# 03-FT601.net
KiCad netlist of a schematic drawn in Altium Designer
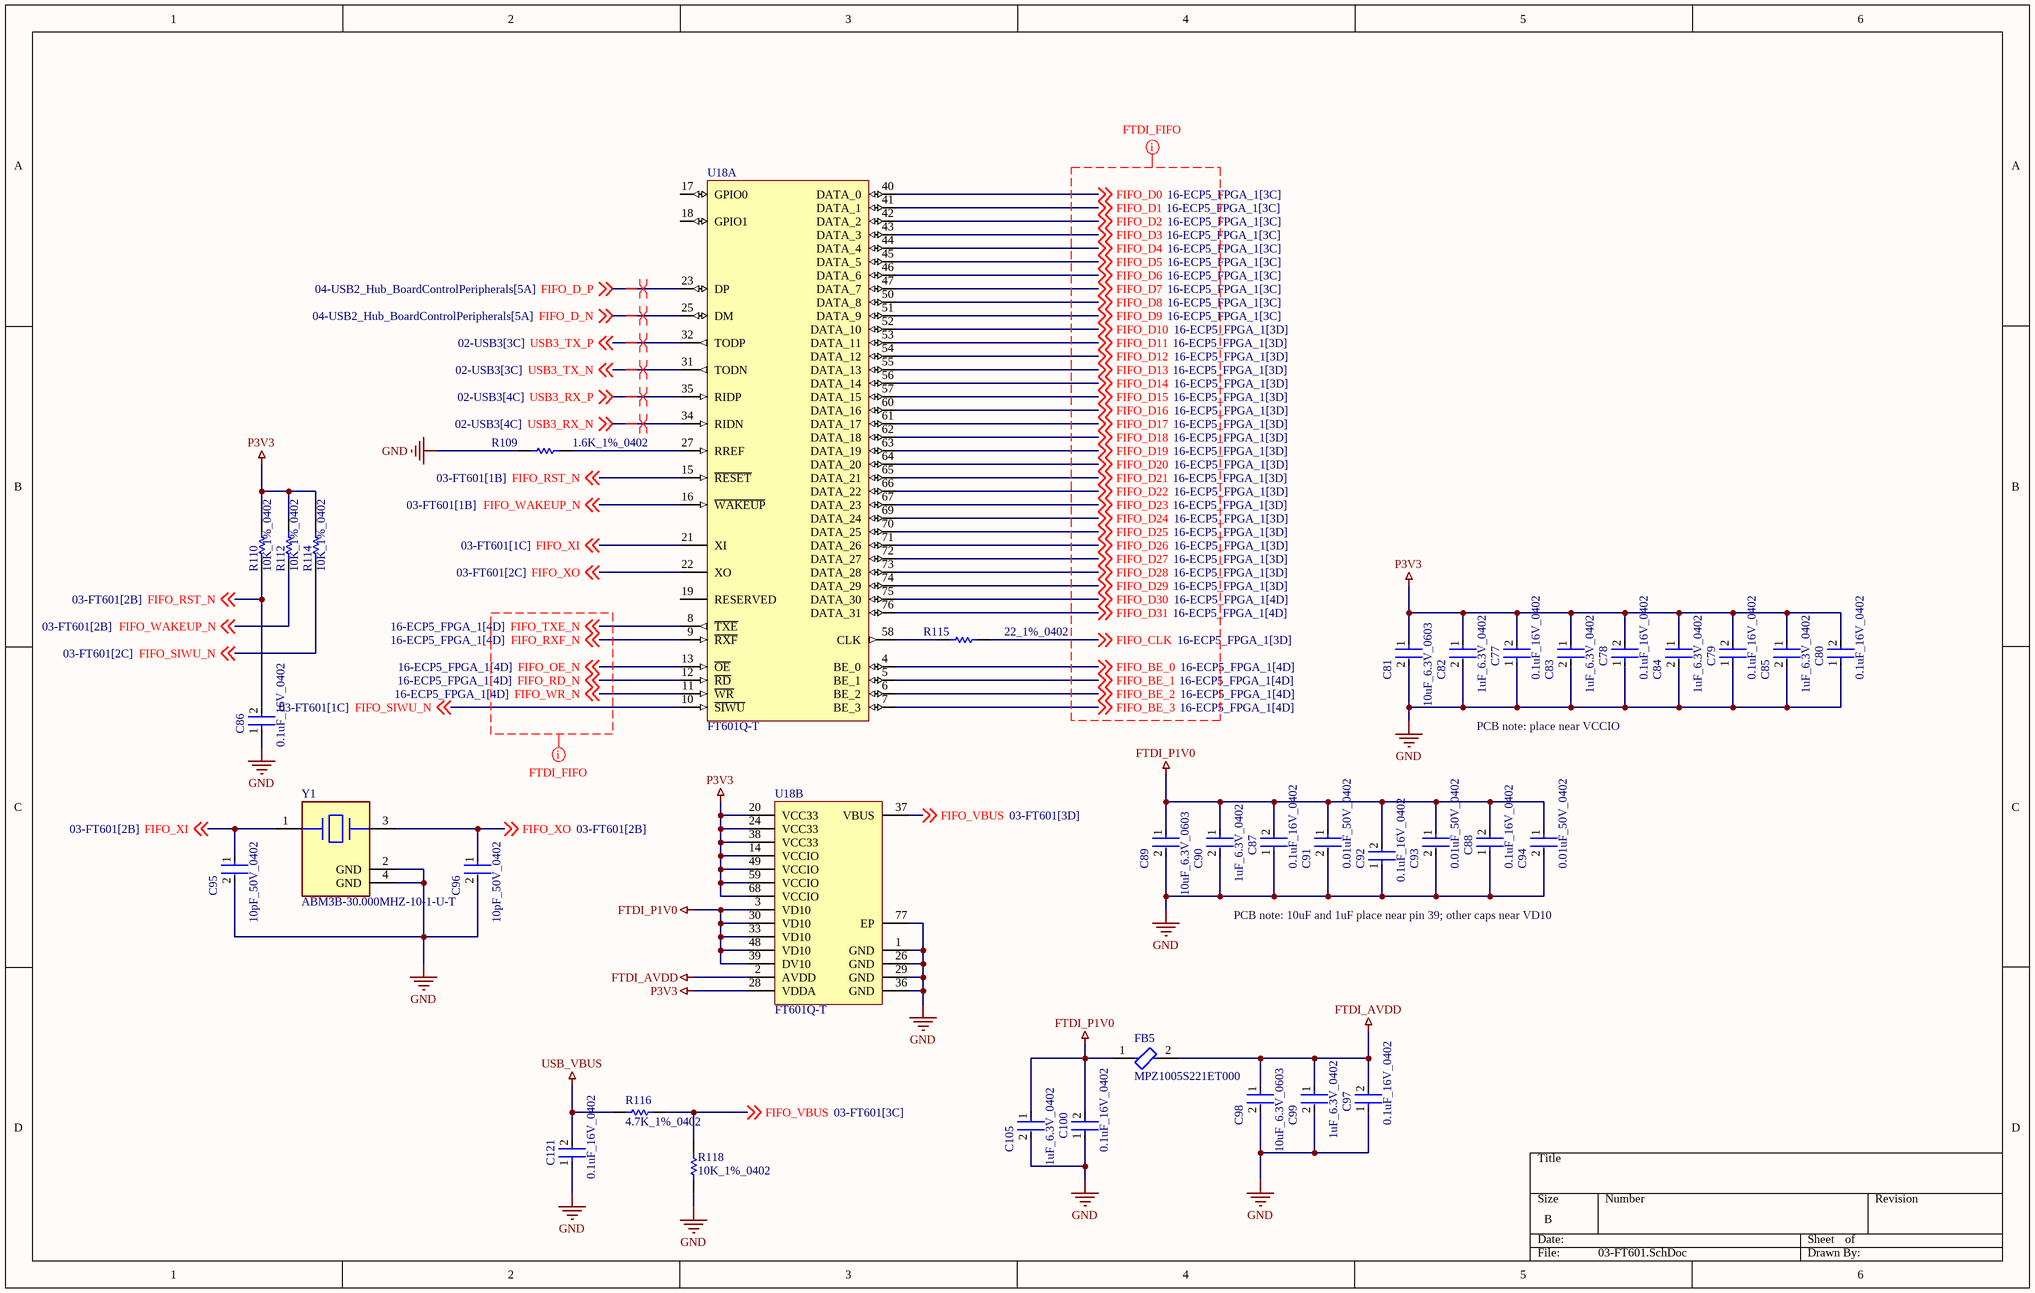
[diagram p0: 03-FT601.SchDoc]

(export (version "E")
  (design (tool "Eeschema 10.0.6"))
  (components
    (comp (ref "C77")
      (value "0.1uF_16V_0402")
      (footprint "FP-C0402-BB-MFG")
      (description "CAP CER 0.1UF 16V 5% X7R 0402")
      (fields
        (field (name "MANUFACTURER") "Kemet")
        (field (name "MANUFACTURER PART NUMBER") "C0402C104J4RACTU")
      )
      (libsource (lib "Altium Content Vault") (part "b4654b650e69147ec39a6b967a45e02"))
    )
    (comp (ref "C78")
      (value "0.1uF_16V_0402")
      (footprint "FP-C0402-BB-MFG")
      (description "CAP CER 0.1UF 16V 5% X7R 0402")
      (fields
        (field (name "MANUFACTURER") "Kemet")
        (field (name "MANUFACTURER PART NUMBER") "C0402C104J4RACTU")
      )
      (libsource (lib "Altium Content Vault") (part "b4654b650e69147ec39a6b967a45e02"))
    )
    (comp (ref "C79")
      (value "0.1uF_16V_0402")
      (footprint "FP-C0402-BB-MFG")
      (description "CAP CER 0.1UF 16V 5% X7R 0402")
      (fields
        (field (name "MANUFACTURER") "Kemet")
        (field (name "MANUFACTURER PART NUMBER") "C0402C104J4RACTU")
      )
      (libsource (lib "Altium Content Vault") (part "b4654b650e69147ec39a6b967a45e02"))
    )
    (comp (ref "C80")
      (value "0.1uF_16V_0402")
      (footprint "FP-C0402-BB-MFG")
      (description "CAP CER 0.1UF 16V 5% X7R 0402")
      (fields
        (field (name "MANUFACTURER") "Kemet")
        (field (name "MANUFACTURER PART NUMBER") "C0402C104J4RACTU")
      )
      (libsource (lib "Altium Content Vault") (part "b4654b650e69147ec39a6b967a45e02"))
    )
    (comp (ref "C81")
      (value "10uF_6.3V_0603")
      (footprint "FP-GRM188-0_1-e0_2_0_55-IPC_A")
      (description "Chip Multilayer Ceramic Capacitors for General Purpose, 0603, 10uF, X5R, 15%, 20%, 6.3V")
      (fields (field (name "VOLTAGE") "6.3V") (field (name "TOLERANCE") "20%"))
      (libsource (lib "Altium Content Vault") (part "02cd4be3c70576c341d710602a673aa"))
    )
    (comp (ref "C82")
      (value "1uF_6.3V_0402")
      (footprint "FP-CC0402-MFG")
      (description "CAP CER 1UF 6.3V X5R 0402")
      (fields
        (field (name "MANUFACTURER") "YAGEO")
        (field (name "OCTOPART") "https://octopart.com/cc0402krx5r5bb105-yageo-42244618")
      )
      (libsource (lib "Altium Content Vault") (part "11868f565c42a9108669ba33697ecf6"))
    )
    (comp (ref "C83")
      (value "1uF_6.3V_0402")
      (footprint "FP-CC0402-MFG")
      (description "CAP CER 1UF 6.3V X5R 0402")
      (fields
        (field (name "MANUFACTURER") "YAGEO")
        (field (name "OCTOPART") "https://octopart.com/cc0402krx5r5bb105-yageo-42244618")
      )
      (libsource (lib "Altium Content Vault") (part "11868f565c42a9108669ba33697ecf6"))
    )
    (comp (ref "C84")
      (value "1uF_6.3V_0402")
      (footprint "FP-CC0402-MFG")
      (description "CAP CER 1UF 6.3V X5R 0402")
      (fields
        (field (name "MANUFACTURER") "YAGEO")
        (field (name "OCTOPART") "https://octopart.com/cc0402krx5r5bb105-yageo-42244618")
      )
      (libsource (lib "Altium Content Vault") (part "11868f565c42a9108669ba33697ecf6"))
    )
    (comp (ref "C85")
      (value "1uF_6.3V_0402")
      (footprint "FP-CC0402-MFG")
      (description "CAP CER 1UF 6.3V X5R 0402")
      (fields
        (field (name "MANUFACTURER") "YAGEO")
        (field (name "OCTOPART") "https://octopart.com/cc0402krx5r5bb105-yageo-42244618")
      )
      (libsource (lib "Altium Content Vault") (part "11868f565c42a9108669ba33697ecf6"))
    )
    (comp (ref "C86")
      (value "0.1uF_16V_0402")
      (footprint "FP-C0402-BB-MFG")
      (description "CAP CER 0.1UF 16V 5% X7R 0402")
      (fields
        (field (name "MANUFACTURER") "Kemet")
        (field (name "MANUFACTURER PART NUMBER") "C0402C104J4RACTU")
      )
      (libsource (lib "Altium Content Vault") (part "b4654b650e69147ec39a6b967a45e02"))
    )
    (comp (ref "C87")
      (value "0.1uF_16V_0402")
      (footprint "FP-C0402-BB-MFG")
      (description "CAP CER 0.1UF 16V 5% X7R 0402")
      (fields
        (field (name "MANUFACTURER") "Kemet")
        (field (name "MANUFACTURER PART NUMBER") "C0402C104J4RACTU")
      )
      (libsource (lib "Altium Content Vault") (part "b4654b650e69147ec39a6b967a45e02"))
    )
    (comp (ref "C88")
      (value "0.1uF_16V_0402")
      (footprint "FP-C0402-BB-MFG")
      (description "CAP CER 0.1UF 16V 5% X7R 0402")
      (fields
        (field (name "MANUFACTURER") "Kemet")
        (field (name "MANUFACTURER PART NUMBER") "C0402C104J4RACTU")
      )
      (libsource (lib "Altium Content Vault") (part "b4654b650e69147ec39a6b967a45e02"))
    )
    (comp (ref "C89")
      (value "10uF_6.3V_0603")
      (footprint "FP-GRM188-0_1-e0_2_0_55-IPC_A")
      (description "Chip Multilayer Ceramic Capacitors for General Purpose, 0603, 10uF, X5R, 15%, 20%, 6.3V")
      (fields (field (name "VOLTAGE") "6.3V") (field (name "TOLERANCE") "20%"))
      (libsource (lib "Altium Content Vault") (part "02cd4be3c70576c341d710602a673aa"))
    )
    (comp (ref "C90")
      (value "1uF_6.3V_0402")
      (footprint "FP-CC0402-MFG")
      (description "CAP CER 1UF 6.3V X5R 0402")
      (fields
        (field (name "MANUFACTURER") "YAGEO")
        (field (name "OCTOPART") "https://octopart.com/cc0402krx5r5bb105-yageo-42244618")
      )
      (libsource (lib "Altium Content Vault") (part "11868f565c42a9108669ba33697ecf6"))
    )
    (comp (ref "C91")
      (value "0.01uF_50V_0402")
      (footprint "FP-C0402-BB-MFG")
      (description "CAP CER 10000PF 50V X7R 0402")
      (fields (field (name "TOLERANCE") "0.1") (field (name "MANUFACTURER") "Kemet"))
      (libsource (lib "Altium Content Vault") (part "b4654b650e69147ec39a6b967a45e02"))
    )
    (comp (ref "C92")
      (value "0.1uF_16V_0402")
      (footprint "FP-C0402-BB-MFG")
      (description "CAP CER 0.1UF 16V 5% X7R 0402")
      (fields
        (field (name "MANUFACTURER") "Kemet")
        (field (name "MANUFACTURER PART NUMBER") "C0402C104J4RACTU")
      )
      (libsource (lib "Altium Content Vault") (part "b4654b650e69147ec39a6b967a45e02"))
    )
    (comp (ref "C93")
      (value "0.01uF_50V_0402")
      (footprint "FP-C0402-BB-MFG")
      (description "CAP CER 10000PF 50V X7R 0402")
      (fields (field (name "TOLERANCE") "0.1") (field (name "MANUFACTURER") "Kemet"))
      (libsource (lib "Altium Content Vault") (part "b4654b650e69147ec39a6b967a45e02"))
    )
    (comp (ref "C94")
      (value "0.01uF_50V_0402")
      (footprint "FP-C0402-BB-MFG")
      (description "CAP CER 10000PF 50V X7R 0402")
      (fields (field (name "TOLERANCE") "0.1") (field (name "MANUFACTURER") "Kemet"))
      (libsource (lib "Altium Content Vault") (part "b4654b650e69147ec39a6b967a45e02"))
    )
    (comp (ref "C95")
      (value "10pF_50V_0402")
      (footprint "FP-C0402-BB-MFG")
      (fields
        (field (name "MANUFACTURER PART NUMBER") "C0402C100J5GACTU")
        (field (name "MANUFACTURER") "Kemet")
        (field (name "OCTOPART") "https://octopart.com/c0402c100j5gactu-kemet-108448")
      )
      (libsource (lib "Altium Content Vault") (part "b4654b650e69147ec39a6b967a45e02"))
    )
    (comp (ref "C96")
      (value "10pF_50V_0402")
      (footprint "FP-C0402-BB-MFG")
      (fields
        (field (name "MANUFACTURER PART NUMBER") "C0402C100J5GACTU")
        (field (name "MANUFACTURER") "Kemet")
        (field (name "OCTOPART") "https://octopart.com/c0402c100j5gactu-kemet-108448")
      )
      (libsource (lib "Altium Content Vault") (part "b4654b650e69147ec39a6b967a45e02"))
    )
    (comp (ref "C97")
      (value "0.1uF_16V_0402")
      (footprint "FP-C0402-BB-MFG")
      (description "CAP CER 0.1UF 16V 5% X7R 0402")
      (fields
        (field (name "MANUFACTURER") "Kemet")
        (field (name "MANUFACTURER PART NUMBER") "C0402C104J4RACTU")
      )
      (libsource (lib "Altium Content Vault") (part "b4654b650e69147ec39a6b967a45e02"))
    )
    (comp (ref "C98")
      (value "10uF_6.3V_0603")
      (footprint "FP-GRM188-0_1-e0_2_0_55-IPC_A")
      (description "Chip Multilayer Ceramic Capacitors for General Purpose, 0603, 10uF, X5R, 15%, 20%, 6.3V")
      (fields (field (name "VOLTAGE") "6.3V") (field (name "TOLERANCE") "20%"))
      (libsource (lib "Altium Content Vault") (part "02cd4be3c70576c341d710602a673aa"))
    )
    (comp (ref "C99")
      (value "1uF_6.3V_0402")
      (footprint "FP-CC0402-MFG")
      (description "CAP CER 1UF 6.3V X5R 0402")
      (fields
        (field (name "MANUFACTURER") "YAGEO")
        (field (name "OCTOPART") "https://octopart.com/cc0402krx5r5bb105-yageo-42244618")
      )
      (libsource (lib "Altium Content Vault") (part "11868f565c42a9108669ba33697ecf6"))
    )
    (comp (ref "C100")
      (value "0.1uF_16V_0402")
      (footprint "FP-C0402-BB-MFG")
      (description "CAP CER 0.1UF 16V 5% X7R 0402")
      (fields
        (field (name "MANUFACTURER") "Kemet")
        (field (name "MANUFACTURER PART NUMBER") "C0402C104J4RACTU")
      )
      (libsource (lib "Altium Content Vault") (part "b4654b650e69147ec39a6b967a45e02"))
    )
    (comp (ref "C105")
      (value "1uF_6.3V_0402")
      (footprint "FP-CC0402-MFG")
      (description "CAP CER 1UF 6.3V X5R 0402")
      (fields
        (field (name "MANUFACTURER") "YAGEO")
        (field (name "OCTOPART") "https://octopart.com/cc0402krx5r5bb105-yageo-42244618")
      )
      (libsource (lib "Altium Content Vault") (part "11868f565c42a9108669ba33697ecf6"))
    )
    (comp (ref "C121")
      (value "0.1uF_16V_0402")
      (footprint "FP-C0402-BB-MFG")
      (description "CAP CER 0.1UF 16V 5% X7R 0402")
      (fields
        (field (name "MANUFACTURER") "Kemet")
        (field (name "MANUFACTURER PART NUMBER") "C0402C104J4RACTU")
      )
      (libsource (lib "Altium Content Vault") (part "b4654b650e69147ec39a6b967a45e02"))
    )
    (comp (ref "FB5")
      (value "MPZ1005S221ET000")
      (footprint "FP-MPZ1005-IPC_A")
      (description "Power line Ferrite Bead 220Ω @ 100MHz 0.9A DCR 0.22Ω SMD 0402")
      (fields (field (name "TOLERANCE") "25%"))
      (libsource (lib "Altium Content Vault") (part "5f30dd21d616792df468990f7003faa"))
    )
    (comp (ref "R109")
      (value "1.6K_1%_0402")
      (footprint "RESC1005X40X25LL05T05")
      (fields (field (name "MANUFACTURER") "Panasonic") (field (name "PART NUMBER") "ERJ-2RKF1601X"))
      (libsource (lib "Altium Content Vault") (part "RES"))
    )
    (comp (ref "R110")
      (value "10K_1%_0402")
      (footprint "RESC1005X40X25NL10T10")
      (fields (field (name "MANUFACTURER") "Bourns") (field (name "PART NUMBER") "CR0402-FX-1002GLF"))
      (libsource (lib "Altium Content Vault") (part "RES"))
    )
    (comp (ref "R112")
      (value "10K_1%_0402")
      (footprint "RESC1005X40X25NL10T10")
      (fields (field (name "MANUFACTURER") "Bourns") (field (name "PART NUMBER") "CR0402-FX-1002GLF"))
      (libsource (lib "Altium Content Vault") (part "RES"))
    )
    (comp (ref "R114")
      (value "10K_1%_0402")
      (footprint "RESC1005X40X25NL10T10")
      (fields (field (name "MANUFACTURER") "Bourns") (field (name "PART NUMBER") "CR0402-FX-1002GLF"))
      (libsource (lib "Altium Content Vault") (part "RES"))
    )
    (comp (ref "R115")
      (value "22_1%_0402")
      (footprint "RESC1005X40X25ML05T05")
      (description "Chip Resistor, 22 Ohm, +/- 1%, 0.1 W, -55 to 155 degC, 0402 (1005 Metric), RoHS, Tape and Reel")
      (fields (field (name "PARTNUMBER") "ERJ-2RKF22R0X") (field (name "TOLERANCE") "1%"))
      (libsource (lib "Altium Content Vault") (part "RES-2"))
    )
    (comp (ref "R116")
      (value "4.7K_1%_0402")
      (footprint "RESC1005X40X25NL05T10")
      (fields (field (name "MANUFACTURER") "Yageo / Phycomp") (field (name "PART NUMBER") "RC0402FR-074K7L"))
      (libsource (lib "Altium Content Vault") (part "RES"))
    )
    (comp (ref "R118")
      (value "10K_1%_0402")
      (footprint "RESC1005X40X25NL10T10")
      (fields (field (name "MANUFACTURER") "Bourns") (field (name "PART NUMBER") "CR0402-FX-1002GLF"))
      (libsource (lib "Altium Content Vault") (part "RES"))
    )
    (comp (ref "U18")
      (value "FT601Q-T")
      (footprint "FTDI-QFN-76_M")
      (description "32 Bit USB 3.0 to FIFO Bridge, 5 Gbps, 3 to 3.6 V, -40 to 85 degC, 76-Pin QFN, Pb-Free, Tray")
      (libsource (lib "Altium Content Vault") (part "FTDI-FT601Q-QFN-76"))
    )
    (comp (ref "Y1")
      (value "ABM3B-30.000MHZ-10-1-U-T")
      (footprint "FP-ABM3B-MFG")
      (description "Crystal 30MHz ±10ppm 10pF SMD-4 5mm x 3.2mm")
      (fields (field (name "TOLERANCE") "10ppm"))
      (libsource (lib "Altium Content Vault") (part "48e526d86b7f2615d98721063c72f49"))
    )
  )
  (nets
    (net (code "1") (name "FIFO_BE_0") (class "Default")
      (node (ref "U18") (pin "4") (pinfunction "BE_0_4") (pintype "bidirectional"))
    )
    (net (code "2") (name "FIFO_BE_1") (class "Default")
      (node (ref "U18") (pin "5") (pinfunction "BE_1_5") (pintype "bidirectional"))
    )
    (net (code "3") (name "FIFO_BE_2") (class "Default")
      (node (ref "U18") (pin "6") (pinfunction "BE_2_6") (pintype "bidirectional"))
    )
    (net (code "4") (name "FIFO_BE_3") (class "Default")
      (node (ref "U18") (pin "7") (pinfunction "BE_3_7") (pintype "bidirectional"))
    )
    (net (code "5") (name "FIFO_CLK") (class "Default")
      (node (ref "R115") (pin "2") (pinfunction "2_2") (pintype "passive"))
    )
    (net (code "6") (name "FIFO_D0") (class "Default")
      (node (ref "U18") (pin "40") (pinfunction "DATA_0_40") (pintype "bidirectional"))
    )
    (net (code "7") (name "FIFO_D1") (class "Default")
      (node (ref "U18") (pin "41") (pinfunction "DATA_1_41") (pintype "bidirectional"))
    )
    (net (code "8") (name "FIFO_D2") (class "Default")
      (node (ref "U18") (pin "42") (pinfunction "DATA_2_42") (pintype "bidirectional"))
    )
    (net (code "9") (name "FIFO_D3") (class "Default")
      (node (ref "U18") (pin "43") (pinfunction "DATA_3_43") (pintype "bidirectional"))
    )
    (net (code "10") (name "FIFO_D4") (class "Default")
      (node (ref "U18") (pin "44") (pinfunction "DATA_4_44") (pintype "bidirectional"))
    )
    (net (code "11") (name "FIFO_D5") (class "Default")
      (node (ref "U18") (pin "45") (pinfunction "DATA_5_45") (pintype "bidirectional"))
    )
    (net (code "12") (name "FIFO_D6") (class "Default")
      (node (ref "U18") (pin "46") (pinfunction "DATA_6_46") (pintype "bidirectional"))
    )
    (net (code "13") (name "FIFO_D7") (class "Default")
      (node (ref "U18") (pin "47") (pinfunction "DATA_7_47") (pintype "bidirectional"))
    )
    (net (code "14") (name "FIFO_D8") (class "Default")
      (node (ref "U18") (pin "50") (pinfunction "DATA_8_50") (pintype "bidirectional"))
    )
    (net (code "15") (name "FIFO_D9") (class "Default")
      (node (ref "U18") (pin "51") (pinfunction "DATA_9_51") (pintype "bidirectional"))
    )
    (net (code "16") (name "FIFO_D10") (class "Default")
      (node (ref "U18") (pin "52") (pinfunction "DATA_10_52") (pintype "bidirectional"))
    )
    (net (code "17") (name "FIFO_D11") (class "Default")
      (node (ref "U18") (pin "53") (pinfunction "DATA_11_53") (pintype "bidirectional"))
    )
    (net (code "18") (name "FIFO_D12") (class "Default")
      (node (ref "U18") (pin "54") (pinfunction "DATA_12_54") (pintype "bidirectional"))
    )
    (net (code "19") (name "FIFO_D13") (class "Default")
      (node (ref "U18") (pin "55") (pinfunction "DATA_13_55") (pintype "bidirectional"))
    )
    (net (code "20") (name "FIFO_D14") (class "Default")
      (node (ref "U18") (pin "56") (pinfunction "DATA_14_56") (pintype "bidirectional"))
    )
    (net (code "21") (name "FIFO_D15") (class "Default")
      (node (ref "U18") (pin "57") (pinfunction "DATA_15_57") (pintype "bidirectional"))
    )
    (net (code "22") (name "FIFO_D16") (class "Default")
      (node (ref "U18") (pin "60") (pinfunction "DATA_16_60") (pintype "bidirectional"))
    )
    (net (code "23") (name "FIFO_D17") (class "Default")
      (node (ref "U18") (pin "61") (pinfunction "DATA_17_61") (pintype "bidirectional"))
    )
    (net (code "24") (name "FIFO_D18") (class "Default")
      (node (ref "U18") (pin "62") (pinfunction "DATA_18_62") (pintype "bidirectional"))
    )
    (net (code "25") (name "FIFO_D19") (class "Default")
      (node (ref "U18") (pin "63") (pinfunction "DATA_19_63") (pintype "bidirectional"))
    )
    (net (code "26") (name "FIFO_D20") (class "Default")
      (node (ref "U18") (pin "64") (pinfunction "DATA_20_64") (pintype "bidirectional"))
    )
    (net (code "27") (name "FIFO_D21") (class "Default")
      (node (ref "U18") (pin "65") (pinfunction "DATA_21_65") (pintype "bidirectional"))
    )
    (net (code "28") (name "FIFO_D22") (class "Default")
      (node (ref "U18") (pin "66") (pinfunction "DATA_22_66") (pintype "bidirectional"))
    )
    (net (code "29") (name "FIFO_D23") (class "Default")
      (node (ref "U18") (pin "67") (pinfunction "DATA_23_67") (pintype "bidirectional"))
    )
    (net (code "30") (name "FIFO_D24") (class "Default")
      (node (ref "U18") (pin "69") (pinfunction "DATA_24_69") (pintype "bidirectional"))
    )
    (net (code "31") (name "FIFO_D25") (class "Default")
      (node (ref "U18") (pin "70") (pinfunction "DATA_25_70") (pintype "bidirectional"))
    )
    (net (code "32") (name "FIFO_D26") (class "Default")
      (node (ref "U18") (pin "71") (pinfunction "DATA_26_71") (pintype "bidirectional"))
    )
    (net (code "33") (name "FIFO_D27") (class "Default")
      (node (ref "U18") (pin "72") (pinfunction "DATA_27_72") (pintype "bidirectional"))
    )
    (net (code "34") (name "FIFO_D28") (class "Default")
      (node (ref "U18") (pin "73") (pinfunction "DATA_28_73") (pintype "bidirectional"))
    )
    (net (code "35") (name "FIFO_D29") (class "Default")
      (node (ref "U18") (pin "74") (pinfunction "DATA_29_74") (pintype "bidirectional"))
    )
    (net (code "36") (name "FIFO_D30") (class "Default")
      (node (ref "U18") (pin "75") (pinfunction "DATA_30_75") (pintype "bidirectional"))
    )
    (net (code "37") (name "FIFO_D31") (class "Default")
      (node (ref "U18") (pin "76") (pinfunction "DATA_31_76") (pintype "bidirectional"))
    )
    (net (code "38") (name "FIFO_D_N") (class "Default")
      (node (ref "U18") (pin "25") (pinfunction "DM_25") (pintype "bidirectional"))
    )
    (net (code "39") (name "FIFO_D_P") (class "Default")
      (node (ref "U18") (pin "23") (pinfunction "DP_23") (pintype "bidirectional"))
    )
    (net (code "40") (name "FIFO_OE_N") (class "Default")
      (node (ref "U18") (pin "13") (pinfunction "~{OE}_13") (pintype "input"))
    )
    (net (code "41") (name "FIFO_RD_N") (class "Default")
      (node (ref "U18") (pin "12") (pinfunction "~{RD}_12") (pintype "input"))
    )
    (net (code "42") (name "FIFO_RST_N") (class "Default")
      (node (ref "C86") (pin "2") (pinfunction "2_2") (pintype "passive"))
      (node (ref "R110") (pin "2") (pinfunction "2_2") (pintype "passive"))
      (node (ref "U18") (pin "15") (pinfunction "~{RESET}_15") (pintype "input"))
    )
    (net (code "43") (name "FIFO_RXF_N") (class "Default")
      (node (ref "U18") (pin "9") (pinfunction "~{RXF}_9") (pintype "input"))
    )
    (net (code "44") (name "FIFO_SIWU_N") (class "Default")
      (node (ref "R114") (pin "2") (pinfunction "2_2") (pintype "passive"))
      (node (ref "U18") (pin "10") (pinfunction "~{SIWU}_10") (pintype "input"))
    )
    (net (code "45") (name "FIFO_TXE_N") (class "Default")
      (node (ref "U18") (pin "8") (pinfunction "~{TXE}_8") (pintype "output"))
    )
    (net (code "46") (name "FIFO_VBUS") (class "Default")
      (node (ref "R116") (pin "2") (pinfunction "2_2") (pintype "passive"))
      (node (ref "R118") (pin "1") (pinfunction "1_1") (pintype "passive"))
      (node (ref "U18") (pin "37") (pinfunction "VBUS_37") (pintype "power_in"))
    )
    (net (code "47") (name "FIFO_WAKEUP_N") (class "Default")
      (node (ref "R112") (pin "2") (pinfunction "2_2") (pintype "passive"))
      (node (ref "U18") (pin "16") (pinfunction "~{WAKEUP}_16") (pintype "input"))
    )
    (net (code "48") (name "FIFO_WR_N") (class "Default")
      (node (ref "U18") (pin "11") (pinfunction "~{WR}_11") (pintype "input"))
    )
    (net (code "49") (name "FIFO_XI") (class "Default")
      (node (ref "C95") (pin "1") (pinfunction "1_1") (pintype "passive"))
      (node (ref "U18") (pin "21") (pinfunction "XI_21") (pintype "passive"))
      (node (ref "Y1") (pin "1") (pinfunction "1_1") (pintype "passive"))
    )
    (net (code "50") (name "FIFO_XO") (class "Default")
      (node (ref "C96") (pin "1") (pinfunction "1_1") (pintype "passive"))
      (node (ref "U18") (pin "22") (pinfunction "XO_22") (pintype "passive"))
      (node (ref "Y1") (pin "3") (pinfunction "3_3") (pintype "passive"))
    )
    (net (code "51") (name "FTDI_AVDD") (class "Default")
      (node (ref "C97") (pin "2") (pinfunction "2_2") (pintype "passive"))
      (node (ref "C98") (pin "1") (pinfunction "1_1") (pintype "passive"))
      (node (ref "C99") (pin "1") (pinfunction "1_1") (pintype "passive"))
      (node (ref "FB5") (pin "2") (pinfunction "2_2") (pintype "passive"))
      (node (ref "U18") (pin "2") (pinfunction "AVDD_2") (pintype "power_in"))
    )
    (net (code "52") (name "FTDI_P1V0") (class "Default")
      (node (ref "C100") (pin "2") (pinfunction "2_2") (pintype "passive"))
      (node (ref "C105") (pin "1") (pinfunction "1_1") (pintype "passive"))
      (node (ref "C87") (pin "2") (pinfunction "2_2") (pintype "passive"))
      (node (ref "C88") (pin "2") (pinfunction "2_2") (pintype "passive"))
      (node (ref "C89") (pin "1") (pinfunction "1_1") (pintype "passive"))
      (node (ref "C90") (pin "1") (pinfunction "1_1") (pintype "passive"))
      (node (ref "C91") (pin "1") (pinfunction "1_1") (pintype "passive"))
      (node (ref "C92") (pin "2") (pinfunction "2_2") (pintype "passive"))
      (node (ref "C93") (pin "1") (pinfunction "1_1") (pintype "passive"))
      (node (ref "C94") (pin "1") (pinfunction "1_1") (pintype "passive"))
      (node (ref "FB5") (pin "1") (pinfunction "1_1") (pintype "passive"))
      (node (ref "U18") (pin "3") (pinfunction "VD10_3") (pintype "power_in"))
      (node (ref "U18") (pin "30") (pinfunction "VD10_30") (pintype "power_in"))
      (node (ref "U18") (pin "33") (pinfunction "VD10_33") (pintype "power_in"))
      (node (ref "U18") (pin "39") (pinfunction "DV10_39") (pintype "power_in"))
      (node (ref "U18") (pin "48") (pinfunction "VD10_48") (pintype "power_in"))
    )
    (net (code "53") (name "GND") (class "Default")
      (node (ref "C100") (pin "1") (pinfunction "1_1") (pintype "passive"))
      (node (ref "C105") (pin "2") (pinfunction "2_2") (pintype "passive"))
      (node (ref "C121") (pin "1") (pinfunction "1_1") (pintype "passive"))
      (node (ref "C77") (pin "1") (pinfunction "1_1") (pintype "passive"))
      (node (ref "C78") (pin "1") (pinfunction "1_1") (pintype "passive"))
      (node (ref "C79") (pin "1") (pinfunction "1_1") (pintype "passive"))
      (node (ref "C80") (pin "1") (pinfunction "1_1") (pintype "passive"))
      (node (ref "C81") (pin "2") (pinfunction "2_2") (pintype "passive"))
      (node (ref "C82") (pin "2") (pinfunction "2_2") (pintype "passive"))
      (node (ref "C83") (pin "2") (pinfunction "2_2") (pintype "passive"))
      (node (ref "C84") (pin "2") (pinfunction "2_2") (pintype "passive"))
      (node (ref "C85") (pin "2") (pinfunction "2_2") (pintype "passive"))
      (node (ref "C86") (pin "1") (pinfunction "1_1") (pintype "passive"))
      (node (ref "C87") (pin "1") (pinfunction "1_1") (pintype "passive"))
      (node (ref "C88") (pin "1") (pinfunction "1_1") (pintype "passive"))
      (node (ref "C89") (pin "2") (pinfunction "2_2") (pintype "passive"))
      (node (ref "C90") (pin "2") (pinfunction "2_2") (pintype "passive"))
      (node (ref "C91") (pin "2") (pinfunction "2_2") (pintype "passive"))
      (node (ref "C92") (pin "1") (pinfunction "1_1") (pintype "passive"))
      (node (ref "C93") (pin "2") (pinfunction "2_2") (pintype "passive"))
      (node (ref "C94") (pin "2") (pinfunction "2_2") (pintype "passive"))
      (node (ref "C95") (pin "2") (pinfunction "2_2") (pintype "passive"))
      (node (ref "C96") (pin "2") (pinfunction "2_2") (pintype "passive"))
      (node (ref "C97") (pin "1") (pinfunction "1_1") (pintype "passive"))
      (node (ref "C98") (pin "2") (pinfunction "2_2") (pintype "passive"))
      (node (ref "C99") (pin "2") (pinfunction "2_2") (pintype "passive"))
      (node (ref "R109") (pin "1") (pinfunction "1_1") (pintype "passive"))
      (node (ref "R118") (pin "2") (pinfunction "2_2") (pintype "passive"))
      (node (ref "U18") (pin "1") (pinfunction "GND_1") (pintype "power_in"))
      (node (ref "U18") (pin "26") (pinfunction "GND_26") (pintype "power_in"))
      (node (ref "U18") (pin "29") (pinfunction "GND_29") (pintype "power_in"))
      (node (ref "U18") (pin "36") (pinfunction "GND_36") (pintype "power_in"))
      (node (ref "U18") (pin "77") (pinfunction "EP_77") (pintype "power_in"))
      (node (ref "Y1") (pin "2") (pinfunction "GND_2") (pintype "power_in"))
      (node (ref "Y1") (pin "4") (pinfunction "GND_4") (pintype "power_in"))
    )
    (net (code "54") (name "Net-(U18A-CLK)") (class "Default")
      (node (ref "R115") (pin "1") (pinfunction "1_1") (pintype "passive"))
      (node (ref "U18") (pin "58") (pinfunction "CLK_58") (pintype "output"))
    )
    (net (code "55") (name "Net-(U18A-RREF)") (class "Default")
      (node (ref "R109") (pin "2") (pinfunction "2_2") (pintype "passive"))
      (node (ref "U18") (pin "27") (pinfunction "RREF_27") (pintype "input"))
    )
    (net (code "56") (name "P3V3") (class "Default")
      (node (ref "C77") (pin "2") (pinfunction "2_2") (pintype "passive"))
      (node (ref "C78") (pin "2") (pinfunction "2_2") (pintype "passive"))
      (node (ref "C79") (pin "2") (pinfunction "2_2") (pintype "passive"))
      (node (ref "C80") (pin "2") (pinfunction "2_2") (pintype "passive"))
      (node (ref "C81") (pin "1") (pinfunction "1_1") (pintype "passive"))
      (node (ref "C82") (pin "1") (pinfunction "1_1") (pintype "passive"))
      (node (ref "C83") (pin "1") (pinfunction "1_1") (pintype "passive"))
      (node (ref "C84") (pin "1") (pinfunction "1_1") (pintype "passive"))
      (node (ref "C85") (pin "1") (pinfunction "1_1") (pintype "passive"))
      (node (ref "R110") (pin "1") (pinfunction "1_1") (pintype "passive"))
      (node (ref "R112") (pin "1") (pinfunction "1_1") (pintype "passive"))
      (node (ref "R114") (pin "1") (pinfunction "1_1") (pintype "passive"))
      (node (ref "U18") (pin "14") (pinfunction "VCCIO_14") (pintype "power_in"))
      (node (ref "U18") (pin "20") (pinfunction "VCC33_20") (pintype "power_in"))
      (node (ref "U18") (pin "24") (pinfunction "VCC33_24") (pintype "power_in"))
      (node (ref "U18") (pin "28") (pinfunction "VDDA_28") (pintype "power_in"))
      (node (ref "U18") (pin "38") (pinfunction "VCC33_38") (pintype "power_in"))
      (node (ref "U18") (pin "49") (pinfunction "VCCIO_49") (pintype "power_in"))
      (node (ref "U18") (pin "59") (pinfunction "VCCIO_59") (pintype "power_in"))
      (node (ref "U18") (pin "68") (pinfunction "VCCIO_68") (pintype "power_in"))
    )
    (net (code "57") (name "USB3_RX_N") (class "Default")
      (node (ref "U18") (pin "34") (pinfunction "RIDN_34") (pintype "input"))
    )
    (net (code "58") (name "USB3_RX_P") (class "Default")
      (node (ref "U18") (pin "35") (pinfunction "RIDP_35") (pintype "input"))
    )
    (net (code "59") (name "USB3_TX_N") (class "Default")
      (node (ref "U18") (pin "31") (pinfunction "TODN_31") (pintype "output"))
    )
    (net (code "60") (name "USB3_TX_P") (class "Default")
      (node (ref "U18") (pin "32") (pinfunction "TODP_32") (pintype "output"))
    )
    (net (code "61") (name "USB_VBUS") (class "Default")
      (node (ref "C121") (pin "2") (pinfunction "2_2") (pintype "passive"))
      (node (ref "R116") (pin "1") (pinfunction "1_1") (pintype "passive"))
    )
    (net (code "62") (name "unconnected-(U18A-GPIO0-Pad17)") (class "Default")
      (node (ref "U18") (pin "17") (pinfunction "GPIO0_17") (pintype "bidirectional"))
    )
    (net (code "63") (name "unconnected-(U18A-GPIO1-Pad18)") (class "Default")
      (node (ref "U18") (pin "18") (pinfunction "GPIO1_18") (pintype "bidirectional"))
    )
    (net (code "64") (name "unconnected-(U18A-RESERVED-Pad19)") (class "Default")
      (node (ref "U18") (pin "19") (pinfunction "RESERVED_19") (pintype "passive"))
    )
  )
)
